# Analog_readout1.net
KiCad netlist of a schematic drawn in Altium Designer
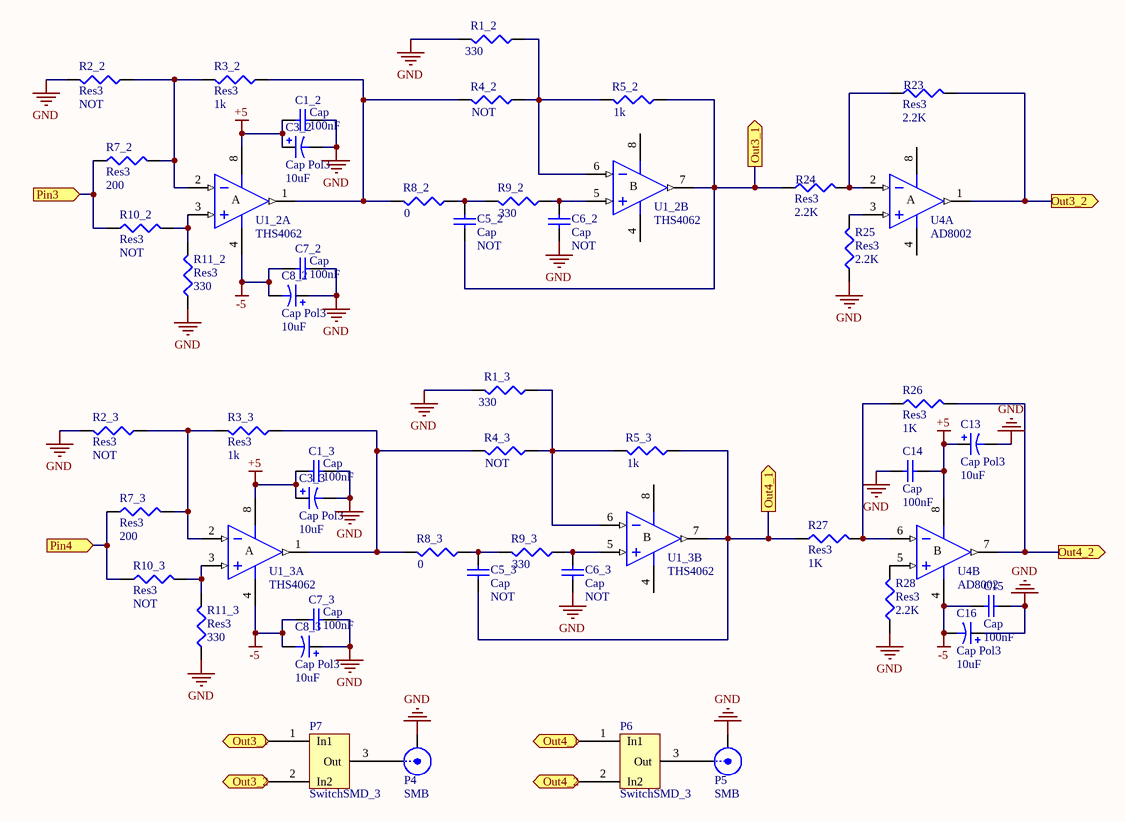
[diagram p0: Analog_readout1.SchDoc]

(export (version "E")
  (design (tool "Eeschema 10.0.6"))
  (components
    (comp (ref "C1_2")
      (value "Cap")
      (footprint "6-0805_N")
      (description "Capacitor")
      (fields (field (name "ALTIUM_VALUE") "100nF") (field (name "PUBLISHER") "Altium Limited"))
      (libsource (lib "Miscellaneous Devices") (part "Cap"))
    )
    (comp (ref "C1_3")
      (value "Cap")
      (footprint "6-0805_N")
      (description "Capacitor")
      (fields (field (name "ALTIUM_VALUE") "100nF") (field (name "PUBLISHER") "Altium Limited"))
      (libsource (lib "Miscellaneous Devices") (part "Cap"))
    )
    (comp (ref "C3_2")
      (value "Cap Pol3")
      (footprint "6-0805_N")
      (description "Polarized Capacitor (Surface Mount)")
      (fields (field (name "ALTIUM_VALUE") "10uF") (field (name "PUBLISHER") "Altium Limited"))
      (libsource (lib "Miscellaneous Devices") (part "Cap Pol3"))
    )
    (comp (ref "C3_3")
      (value "Cap Pol3")
      (footprint "6-0805_N")
      (description "Polarized Capacitor (Surface Mount)")
      (fields (field (name "ALTIUM_VALUE") "10uF") (field (name "PUBLISHER") "Altium Limited"))
      (libsource (lib "Miscellaneous Devices") (part "Cap Pol3"))
    )
    (comp (ref "C5_2")
      (value "Cap")
      (footprint "6-0805_N")
      (description "Capacitor")
      (fields (field (name "ALTIUM_VALUE") "NOT") (field (name "PUBLISHER") "Altium Limited"))
      (libsource (lib "Miscellaneous Devices") (part "Cap"))
    )
    (comp (ref "C5_3")
      (value "Cap")
      (footprint "6-0805_N")
      (description "Capacitor")
      (fields (field (name "ALTIUM_VALUE") "NOT") (field (name "PUBLISHER") "Altium Limited"))
      (libsource (lib "Miscellaneous Devices") (part "Cap"))
    )
    (comp (ref "C6_2")
      (value "Cap")
      (footprint "6-0805_N")
      (description "Capacitor")
      (fields (field (name "ALTIUM_VALUE") "NOT") (field (name "PUBLISHER") "Altium Limited"))
      (libsource (lib "Miscellaneous Devices") (part "Cap"))
    )
    (comp (ref "C6_3")
      (value "Cap")
      (footprint "6-0805_N")
      (description "Capacitor")
      (fields (field (name "ALTIUM_VALUE") "NOT") (field (name "PUBLISHER") "Altium Limited"))
      (libsource (lib "Miscellaneous Devices") (part "Cap"))
    )
    (comp (ref "C7_2")
      (value "Cap")
      (footprint "6-0805_N")
      (description "Capacitor")
      (fields (field (name "ALTIUM_VALUE") "100nF") (field (name "PUBLISHER") "Altium Limited"))
      (libsource (lib "Miscellaneous Devices") (part "Cap"))
    )
    (comp (ref "C7_3")
      (value "Cap")
      (footprint "6-0805_N")
      (description "Capacitor")
      (fields (field (name "ALTIUM_VALUE") "100nF") (field (name "PUBLISHER") "Altium Limited"))
      (libsource (lib "Miscellaneous Devices") (part "Cap"))
    )
    (comp (ref "C8_2")
      (value "Cap Pol3")
      (footprint "6-0805_N")
      (description "Polarized Capacitor (Surface Mount)")
      (fields (field (name "ALTIUM_VALUE") "10uF") (field (name "PUBLISHER") "Altium Limited"))
      (libsource (lib "Miscellaneous Devices") (part "Cap Pol3"))
    )
    (comp (ref "C8_3")
      (value "Cap Pol3")
      (footprint "6-0805_N")
      (description "Polarized Capacitor (Surface Mount)")
      (fields (field (name "ALTIUM_VALUE") "10uF") (field (name "PUBLISHER") "Altium Limited"))
      (libsource (lib "Miscellaneous Devices") (part "Cap Pol3"))
    )
    (comp (ref "C13")
      (value "Cap Pol3")
      (footprint "6-0805_N")
      (description "Polarized Capacitor (Surface Mount)")
      (fields (field (name "ALTIUM_VALUE") "10uF") (field (name "PUBLISHER") "Altium Limited"))
      (libsource (lib "Miscellaneous Devices") (part "Cap Pol3"))
    )
    (comp (ref "C14")
      (value "Cap")
      (footprint "6-0805_N")
      (description "Capacitor")
      (fields (field (name "ALTIUM_VALUE") "100nF") (field (name "PUBLISHER") "Altium Limited"))
      (libsource (lib "Miscellaneous Devices") (part "Cap"))
    )
    (comp (ref "C15")
      (value "Cap")
      (footprint "6-0805_N")
      (description "Capacitor")
      (fields (field (name "ALTIUM_VALUE") "100nF") (field (name "PUBLISHER") "Altium Limited"))
      (libsource (lib "Miscellaneous Devices") (part "Cap"))
    )
    (comp (ref "C16")
      (value "Cap Pol3")
      (footprint "6-0805_N")
      (description "Polarized Capacitor (Surface Mount)")
      (fields (field (name "ALTIUM_VALUE") "10uF") (field (name "PUBLISHER") "Altium Limited"))
      (libsource (lib "Miscellaneous Devices") (part "Cap Pol3"))
    )
    (comp (ref "P4")
      (value "SMB")
      (footprint "SMB_V-RJ45")
      (description "SMB Straight Connector")
      (fields (field (name "PUBLISHER") "Altium Limited"))
      (libsource (lib "Miscellaneous Connectors") (part "SMB"))
    )
    (comp (ref "P5")
      (value "SMB")
      (footprint "SMB_V-RJ45")
      (description "SMB Straight Connector")
      (fields (field (name "PUBLISHER") "Altium Limited"))
      (libsource (lib "Miscellaneous Connectors") (part "SMB"))
    )
    (comp (ref "P6")
      (value "SwitchSMD_3")
      (footprint "SwitchSMD_0603")
      (libsource (lib "Int_Lib1") (part "SwitchSMD_3"))
    )
    (comp (ref "P7")
      (value "SwitchSMD_3")
      (footprint "SwitchSMD_0603")
      (libsource (lib "Int_Lib1") (part "SwitchSMD_3"))
    )
    (comp (ref "R1_2")
      (value "330")
      (footprint "6-0805_N")
      (description "Resistor")
      (fields (field (name "Comment") "Res3") (field (name "PUBLISHER") "Altium Limited"))
      (libsource (lib "Miscellaneous Devices") (part "Res3"))
    )
    (comp (ref "R1_3")
      (value "330")
      (footprint "6-0805_N")
      (description "Resistor")
      (fields (field (name "Comment") "Res3") (field (name "PUBLISHER") "Altium Limited"))
      (libsource (lib "Miscellaneous Devices") (part "Res3"))
    )
    (comp (ref "R2_2")
      (value "Res3")
      (footprint "6-0805_N")
      (description "Resistor")
      (fields (field (name "ALTIUM_VALUE") "NOT") (field (name "PUBLISHER") "Altium Limited"))
      (libsource (lib "Miscellaneous Devices") (part "Res3"))
    )
    (comp (ref "R2_3")
      (value "Res3")
      (footprint "6-0805_N")
      (description "Resistor")
      (fields (field (name "ALTIUM_VALUE") "NOT") (field (name "PUBLISHER") "Altium Limited"))
      (libsource (lib "Miscellaneous Devices") (part "Res3"))
    )
    (comp (ref "R3_2")
      (value "Res3")
      (footprint "6-0805_N")
      (description "Resistor")
      (fields (field (name "ALTIUM_VALUE") "1k") (field (name "PUBLISHER") "Altium Limited"))
      (libsource (lib "Miscellaneous Devices") (part "Res3"))
    )
    (comp (ref "R3_3")
      (value "Res3")
      (footprint "6-0805_N")
      (description "Resistor")
      (fields (field (name "ALTIUM_VALUE") "1k") (field (name "PUBLISHER") "Altium Limited"))
      (libsource (lib "Miscellaneous Devices") (part "Res3"))
    )
    (comp (ref "R4_2")
      (value "NOT")
      (footprint "6-0805_N")
      (description "Resistor")
      (fields (field (name "Comment") "Res3") (field (name "PUBLISHER") "Altium Limited"))
      (libsource (lib "Miscellaneous Devices") (part "Res3"))
    )
    (comp (ref "R4_3")
      (value "NOT")
      (footprint "6-0805_N")
      (description "Resistor")
      (fields (field (name "Comment") "Res3") (field (name "PUBLISHER") "Altium Limited"))
      (libsource (lib "Miscellaneous Devices") (part "Res3"))
    )
    (comp (ref "R5_2")
      (value "1k")
      (footprint "6-0805_N")
      (description "Resistor")
      (fields (field (name "Comment") "Res3") (field (name "PUBLISHER") "Altium Limited"))
      (libsource (lib "Miscellaneous Devices") (part "Res3"))
    )
    (comp (ref "R5_3")
      (value "1k")
      (footprint "6-0805_N")
      (description "Resistor")
      (fields (field (name "Comment") "Res3") (field (name "PUBLISHER") "Altium Limited"))
      (libsource (lib "Miscellaneous Devices") (part "Res3"))
    )
    (comp (ref "R7_2")
      (value "Res3")
      (footprint "6-0805_N")
      (description "Resistor")
      (fields (field (name "ALTIUM_VALUE") "200") (field (name "PUBLISHER") "Altium Limited"))
      (libsource (lib "Miscellaneous Devices") (part "Res3"))
    )
    (comp (ref "R7_3")
      (value "Res3")
      (footprint "6-0805_N")
      (description "Resistor")
      (fields (field (name "ALTIUM_VALUE") "200") (field (name "PUBLISHER") "Altium Limited"))
      (libsource (lib "Miscellaneous Devices") (part "Res3"))
    )
    (comp (ref "R8_2")
      (value "0")
      (footprint "6-0805_N")
      (description "Resistor")
      (fields (field (name "Comment") "Res3") (field (name "PUBLISHER") "Altium Limited"))
      (libsource (lib "Miscellaneous Devices") (part "Res3"))
    )
    (comp (ref "R8_3")
      (value "0")
      (footprint "6-0805_N")
      (description "Resistor")
      (fields (field (name "Comment") "Res3") (field (name "PUBLISHER") "Altium Limited"))
      (libsource (lib "Miscellaneous Devices") (part "Res3"))
    )
    (comp (ref "R9_2")
      (value "330")
      (footprint "6-0805_N")
      (description "Resistor")
      (fields (field (name "Comment") "Res3") (field (name "PUBLISHER") "Altium Limited"))
      (libsource (lib "Miscellaneous Devices") (part "Res3"))
    )
    (comp (ref "R9_3")
      (value "330")
      (footprint "6-0805_N")
      (description "Resistor")
      (fields (field (name "Comment") "Res3") (field (name "PUBLISHER") "Altium Limited"))
      (libsource (lib "Miscellaneous Devices") (part "Res3"))
    )
    (comp (ref "R10_2")
      (value "Res3")
      (footprint "6-0805_N")
      (description "Resistor")
      (fields (field (name "ALTIUM_VALUE") "NOT") (field (name "PUBLISHER") "Altium Limited"))
      (libsource (lib "Miscellaneous Devices") (part "Res3"))
    )
    (comp (ref "R10_3")
      (value "Res3")
      (footprint "6-0805_N")
      (description "Resistor")
      (fields (field (name "ALTIUM_VALUE") "NOT") (field (name "PUBLISHER") "Altium Limited"))
      (libsource (lib "Miscellaneous Devices") (part "Res3"))
    )
    (comp (ref "R11_2")
      (value "Res3")
      (footprint "6-0805_N")
      (description "Resistor")
      (fields (field (name "ALTIUM_VALUE") "330") (field (name "PUBLISHER") "Altium Limited"))
      (libsource (lib "Miscellaneous Devices") (part "Res3"))
    )
    (comp (ref "R11_3")
      (value "Res3")
      (footprint "6-0805_N")
      (description "Resistor")
      (fields (field (name "ALTIUM_VALUE") "330") (field (name "PUBLISHER") "Altium Limited"))
      (libsource (lib "Miscellaneous Devices") (part "Res3"))
    )
    (comp (ref "R23")
      (value "Res3")
      (footprint "6-0805_N")
      (description "Resistor")
      (fields (field (name "ALTIUM_VALUE") "2.2K") (field (name "PUBLISHER") "Altium Limited"))
      (libsource (lib "Miscellaneous Devices") (part "Res3"))
    )
    (comp (ref "R24")
      (value "Res3")
      (footprint "6-0805_N")
      (description "Resistor")
      (fields (field (name "ALTIUM_VALUE") "2.2K") (field (name "PUBLISHER") "Altium Limited"))
      (libsource (lib "Miscellaneous Devices") (part "Res3"))
    )
    (comp (ref "R25")
      (value "Res3")
      (footprint "6-0805_N")
      (description "Resistor")
      (fields (field (name "ALTIUM_VALUE") "2.2K") (field (name "PUBLISHER") "Altium Limited"))
      (libsource (lib "Miscellaneous Devices") (part "Res3"))
    )
    (comp (ref "R26")
      (value "Res3")
      (footprint "6-0805_N")
      (description "Resistor")
      (fields (field (name "ALTIUM_VALUE") "1K") (field (name "PUBLISHER") "Altium Limited"))
      (libsource (lib "Miscellaneous Devices") (part "Res3"))
    )
    (comp (ref "R27")
      (value "Res3")
      (footprint "6-0805_N")
      (description "Resistor")
      (fields (field (name "ALTIUM_VALUE") "1K") (field (name "PUBLISHER") "Altium Limited"))
      (libsource (lib "Miscellaneous Devices") (part "Res3"))
    )
    (comp (ref "R28")
      (value "Res3")
      (footprint "6-0805_N")
      (description "Resistor")
      (fields (field (name "ALTIUM_VALUE") "2.2K") (field (name "PUBLISHER") "Altium Limited"))
      (libsource (lib "Miscellaneous Devices") (part "Res3"))
    )
    (comp (ref "U1_2")
      (value "THS4062")
      (footprint "SO-8_M")
      (description "Dual 600MHz, 50mW Current Feedback Amplifier")
      (fields (field (name "PUBLISHER") "Altium Limited"))
      (libsource (lib "AD Operational Amplifier") (part "AD8002AR"))
    )
    (comp (ref "U1_3")
      (value "THS4062")
      (footprint "SO-8_M")
      (description "Dual 600MHz, 50mW Current Feedback Amplifier")
      (fields (field (name "PUBLISHER") "Altium Limited"))
      (libsource (lib "AD Operational Amplifier") (part "AD8002AR"))
    )
    (comp (ref "U4")
      (value "AD8002")
      (footprint "SO-8_M")
      (description "Dual 600MHz, 50mW Current Feedback Amplifier")
      (fields (field (name "PUBLISHER") "Altium Limited"))
      (libsource (lib "AD Operational Amplifier") (part "AD8002AR"))
    )
  )
  (nets
    (net (code "1") (name "+5") (class "Default")
      (node (ref "C13") (pin "1") (pinfunction "1_1") (pintype "passive"))
      (node (ref "C14") (pin "2") (pinfunction "2_2") (pintype "passive"))
      (node (ref "C1_2") (pin "2") (pinfunction "2_2") (pintype "passive"))
      (node (ref "C1_3") (pin "2") (pinfunction "2_2") (pintype "passive"))
      (node (ref "C3_2") (pin "1") (pinfunction "1_1") (pintype "passive"))
      (node (ref "C3_3") (pin "1") (pinfunction "1_1") (pintype "passive"))
      (node (ref "U1_2") (pin "8") (pinfunction "V+_8") (pintype "power_in"))
      (node (ref "U1_3") (pin "8") (pinfunction "V+_8") (pintype "power_in"))
      (node (ref "U4") (pin "8") (pinfunction "V+_8") (pintype "power_in"))
    )
    (net (code "2") (name "-5") (class "Default")
      (node (ref "C15") (pin "1") (pinfunction "1_1") (pintype "passive"))
      (node (ref "C16") (pin "2") (pinfunction "2_2") (pintype "passive"))
      (node (ref "C7_2") (pin "2") (pinfunction "2_2") (pintype "passive"))
      (node (ref "C7_3") (pin "2") (pinfunction "2_2") (pintype "passive"))
      (node (ref "C8_2") (pin "2") (pinfunction "2_2") (pintype "passive"))
      (node (ref "C8_3") (pin "2") (pinfunction "2_2") (pintype "passive"))
      (node (ref "U1_2") (pin "4") (pinfunction "V-_4") (pintype "power_in"))
      (node (ref "U1_3") (pin "4") (pinfunction "V-_4") (pintype "power_in"))
      (node (ref "U4") (pin "4") (pinfunction "V-_4") (pintype "power_in"))
    )
    (net (code "3") (name "/Out3_1") (class "Default")
      (node (ref "C5_2") (pin "2") (pinfunction "2_2") (pintype "passive"))
      (node (ref "P7") (pin "1") (pinfunction "In1_1") (pintype "passive"))
      (node (ref "R24") (pin "1") (pinfunction "1_1") (pintype "passive"))
      (node (ref "R5_2") (pin "1") (pinfunction "1_1") (pintype "passive"))
      (node (ref "U1_2") (pin "7") (pinfunction "OUT_7") (pintype "output"))
    )
    (net (code "4") (name "/Out3_2") (class "Default")
      (node (ref "P7") (pin "2") (pinfunction "In2_2") (pintype "passive"))
      (node (ref "R23") (pin "2") (pinfunction "2_2") (pintype "passive"))
      (node (ref "U4") (pin "1") (pinfunction "OUT_1") (pintype "output"))
    )
    (net (code "5") (name "/Out4_1") (class "Default")
      (node (ref "C5_3") (pin "2") (pinfunction "2_2") (pintype "passive"))
      (node (ref "P6") (pin "1") (pinfunction "In1_1") (pintype "passive"))
      (node (ref "R27") (pin "1") (pinfunction "1_1") (pintype "passive"))
      (node (ref "R5_3") (pin "1") (pinfunction "1_1") (pintype "passive"))
      (node (ref "U1_3") (pin "7") (pinfunction "OUT_7") (pintype "output"))
    )
    (net (code "6") (name "/Out4_2") (class "Default")
      (node (ref "P6") (pin "2") (pinfunction "In2_2") (pintype "passive"))
      (node (ref "R26") (pin "2") (pinfunction "2_2") (pintype "passive"))
      (node (ref "U4") (pin "7") (pinfunction "OUT_7") (pintype "output"))
    )
    (net (code "7") (name "/Pin3") (class "Default")
      (node (ref "R10_2") (pin "1") (pinfunction "1_1") (pintype "passive"))
      (node (ref "R7_2") (pin "1") (pinfunction "1_1") (pintype "passive"))
    )
    (net (code "8") (name "/Pin4") (class "Default")
      (node (ref "R10_3") (pin "1") (pinfunction "1_1") (pintype "passive"))
      (node (ref "R7_3") (pin "1") (pinfunction "1_1") (pintype "passive"))
    )
    (net (code "9") (name "GND") (class "Default")
      (node (ref "C13") (pin "2") (pinfunction "2_2") (pintype "passive"))
      (node (ref "C14") (pin "1") (pinfunction "1_1") (pintype "passive"))
      (node (ref "C15") (pin "2") (pinfunction "2_2") (pintype "passive"))
      (node (ref "C16") (pin "1") (pinfunction "1_1") (pintype "passive"))
      (node (ref "C1_2") (pin "1") (pinfunction "1_1") (pintype "passive"))
      (node (ref "C1_3") (pin "1") (pinfunction "1_1") (pintype "passive"))
      (node (ref "C3_2") (pin "2") (pinfunction "2_2") (pintype "passive"))
      (node (ref "C3_3") (pin "2") (pinfunction "2_2") (pintype "passive"))
      (node (ref "C6_2") (pin "2") (pinfunction "2_2") (pintype "passive"))
      (node (ref "C6_3") (pin "2") (pinfunction "2_2") (pintype "passive"))
      (node (ref "C7_2") (pin "1") (pinfunction "1_1") (pintype "passive"))
      (node (ref "C7_3") (pin "1") (pinfunction "1_1") (pintype "passive"))
      (node (ref "C8_2") (pin "1") (pinfunction "1_1") (pintype "passive"))
      (node (ref "C8_3") (pin "1") (pinfunction "1_1") (pintype "passive"))
      (node (ref "P4") (pin "2") (pinfunction "Y_2") (pintype "passive"))
      (node (ref "P5") (pin "2") (pinfunction "Y_2") (pintype "passive"))
      (node (ref "R11_2") (pin "1") (pinfunction "1_1") (pintype "passive"))
      (node (ref "R11_3") (pin "1") (pinfunction "1_1") (pintype "passive"))
      (node (ref "R1_2") (pin "2") (pinfunction "2_2") (pintype "passive"))
      (node (ref "R1_3") (pin "2") (pinfunction "2_2") (pintype "passive"))
      (node (ref "R25") (pin "1") (pinfunction "1_1") (pintype "passive"))
      (node (ref "R28") (pin "1") (pinfunction "1_1") (pintype "passive"))
      (node (ref "R2_2") (pin "2") (pinfunction "2_2") (pintype "passive"))
      (node (ref "R2_3") (pin "2") (pinfunction "2_2") (pintype "passive"))
    )
    (net (code "10") (name "Net-(C5_2-Pad1)") (class "Default")
      (node (ref "C5_2") (pin "1") (pinfunction "1_1") (pintype "passive"))
      (node (ref "R8_2") (pin "1") (pinfunction "1_1") (pintype "passive"))
      (node (ref "R9_2") (pin "2") (pinfunction "2_2") (pintype "passive"))
    )
    (net (code "11") (name "Net-(C5_3-Pad1)") (class "Default")
      (node (ref "C5_3") (pin "1") (pinfunction "1_1") (pintype "passive"))
      (node (ref "R8_3") (pin "1") (pinfunction "1_1") (pintype "passive"))
      (node (ref "R9_3") (pin "2") (pinfunction "2_2") (pintype "passive"))
    )
    (net (code "12") (name "Net-(P4-X)") (class "Default")
      (node (ref "P4") (pin "1") (pinfunction "X_1") (pintype "passive"))
      (node (ref "P7") (pin "3") (pinfunction "Out_3") (pintype "passive"))
    )
    (net (code "13") (name "Net-(P5-X)") (class "Default")
      (node (ref "P5") (pin "1") (pinfunction "X_1") (pintype "passive"))
      (node (ref "P6") (pin "3") (pinfunction "Out_3") (pintype "passive"))
    )
    (net (code "14") (name "Net-(U1_2A-IN+)") (class "Default")
      (node (ref "R10_2") (pin "2") (pinfunction "2_2") (pintype "passive"))
      (node (ref "R11_2") (pin "2") (pinfunction "2_2") (pintype "passive"))
      (node (ref "U1_2") (pin "3") (pinfunction "IN+_3") (pintype "input"))
    )
    (net (code "15") (name "Net-(U1_2A-IN-)") (class "Default")
      (node (ref "R2_2") (pin "1") (pinfunction "1_1") (pintype "passive"))
      (node (ref "R3_2") (pin "2") (pinfunction "2_2") (pintype "passive"))
      (node (ref "R7_2") (pin "2") (pinfunction "2_2") (pintype "passive"))
      (node (ref "U1_2") (pin "2") (pinfunction "IN-_2") (pintype "input"))
    )
    (net (code "16") (name "Net-(U1_2A-OUT)") (class "Default")
      (node (ref "R3_2") (pin "1") (pinfunction "1_1") (pintype "passive"))
      (node (ref "R4_2") (pin "2") (pinfunction "2_2") (pintype "passive"))
      (node (ref "R8_2") (pin "2") (pinfunction "2_2") (pintype "passive"))
      (node (ref "U1_2") (pin "1") (pinfunction "OUT_1") (pintype "output"))
    )
    (net (code "17") (name "Net-(U1_2B-IN+)") (class "Default")
      (node (ref "C6_2") (pin "1") (pinfunction "1_1") (pintype "passive"))
      (node (ref "R9_2") (pin "1") (pinfunction "1_1") (pintype "passive"))
      (node (ref "U1_2") (pin "5") (pinfunction "IN+_5") (pintype "input"))
    )
    (net (code "18") (name "Net-(U1_2B-IN-)") (class "Default")
      (node (ref "R1_2") (pin "1") (pinfunction "1_1") (pintype "passive"))
      (node (ref "R4_2") (pin "1") (pinfunction "1_1") (pintype "passive"))
      (node (ref "R5_2") (pin "2") (pinfunction "2_2") (pintype "passive"))
      (node (ref "U1_2") (pin "6") (pinfunction "IN-_6") (pintype "input"))
    )
    (net (code "19") (name "Net-(U1_3A-IN+)") (class "Default")
      (node (ref "R10_3") (pin "2") (pinfunction "2_2") (pintype "passive"))
      (node (ref "R11_3") (pin "2") (pinfunction "2_2") (pintype "passive"))
      (node (ref "U1_3") (pin "3") (pinfunction "IN+_3") (pintype "input"))
    )
    (net (code "20") (name "Net-(U1_3A-IN-)") (class "Default")
      (node (ref "R2_3") (pin "1") (pinfunction "1_1") (pintype "passive"))
      (node (ref "R3_3") (pin "2") (pinfunction "2_2") (pintype "passive"))
      (node (ref "R7_3") (pin "2") (pinfunction "2_2") (pintype "passive"))
      (node (ref "U1_3") (pin "2") (pinfunction "IN-_2") (pintype "input"))
    )
    (net (code "21") (name "Net-(U1_3A-OUT)") (class "Default")
      (node (ref "R3_3") (pin "1") (pinfunction "1_1") (pintype "passive"))
      (node (ref "R4_3") (pin "2") (pinfunction "2_2") (pintype "passive"))
      (node (ref "R8_3") (pin "2") (pinfunction "2_2") (pintype "passive"))
      (node (ref "U1_3") (pin "1") (pinfunction "OUT_1") (pintype "output"))
    )
    (net (code "22") (name "Net-(U1_3B-IN+)") (class "Default")
      (node (ref "C6_3") (pin "1") (pinfunction "1_1") (pintype "passive"))
      (node (ref "R9_3") (pin "1") (pinfunction "1_1") (pintype "passive"))
      (node (ref "U1_3") (pin "5") (pinfunction "IN+_5") (pintype "input"))
    )
    (net (code "23") (name "Net-(U1_3B-IN-)") (class "Default")
      (node (ref "R1_3") (pin "1") (pinfunction "1_1") (pintype "passive"))
      (node (ref "R4_3") (pin "1") (pinfunction "1_1") (pintype "passive"))
      (node (ref "R5_3") (pin "2") (pinfunction "2_2") (pintype "passive"))
      (node (ref "U1_3") (pin "6") (pinfunction "IN-_6") (pintype "input"))
    )
    (net (code "24") (name "Net-(U4A-IN+)") (class "Default")
      (node (ref "R25") (pin "2") (pinfunction "2_2") (pintype "passive"))
      (node (ref "U4") (pin "3") (pinfunction "IN+_3") (pintype "input"))
    )
    (net (code "25") (name "Net-(U4A-IN-)") (class "Default")
      (node (ref "R23") (pin "1") (pinfunction "1_1") (pintype "passive"))
      (node (ref "R24") (pin "2") (pinfunction "2_2") (pintype "passive"))
      (node (ref "U4") (pin "2") (pinfunction "IN-_2") (pintype "input"))
    )
    (net (code "26") (name "Net-(U4B-IN+)") (class "Default")
      (node (ref "R28") (pin "2") (pinfunction "2_2") (pintype "passive"))
      (node (ref "U4") (pin "5") (pinfunction "IN+_5") (pintype "input"))
    )
    (net (code "27") (name "Net-(U4B-IN-)") (class "Default")
      (node (ref "R26") (pin "1") (pinfunction "1_1") (pintype "passive"))
      (node (ref "R27") (pin "2") (pinfunction "2_2") (pintype "passive"))
      (node (ref "U4") (pin "6") (pinfunction "IN-_6") (pintype "input"))
    )
    (net (code "28") (name "unconnected-(U1_2B-V+-Pad8)") (class "Default")
      (node (ref "U1_2") (pin "8") (pinfunction "V+_8") (pintype "power_in"))
    )
    (net (code "29") (name "unconnected-(U1_2B-V--Pad4)") (class "Default")
      (node (ref "U1_2") (pin "4") (pinfunction "V-_4") (pintype "power_in"))
    )
    (net (code "30") (name "unconnected-(U1_3B-V+-Pad8)") (class "Default")
      (node (ref "U1_3") (pin "8") (pinfunction "V+_8") (pintype "power_in"))
    )
    (net (code "31") (name "unconnected-(U1_3B-V--Pad4)") (class "Default")
      (node (ref "U1_3") (pin "4") (pinfunction "V-_4") (pintype "power_in"))
    )
    (net (code "32") (name "unconnected-(U4A-V+-Pad8)") (class "Default")
      (node (ref "U4") (pin "8") (pinfunction "V+_8") (pintype "power_in"))
    )
    (net (code "33") (name "unconnected-(U4A-V--Pad4)") (class "Default")
      (node (ref "U4") (pin "4") (pinfunction "V-_4") (pintype "power_in"))
    )
  )
)
